# Motors.net
KiCad netlist of a schematic drawn in Altium Designer
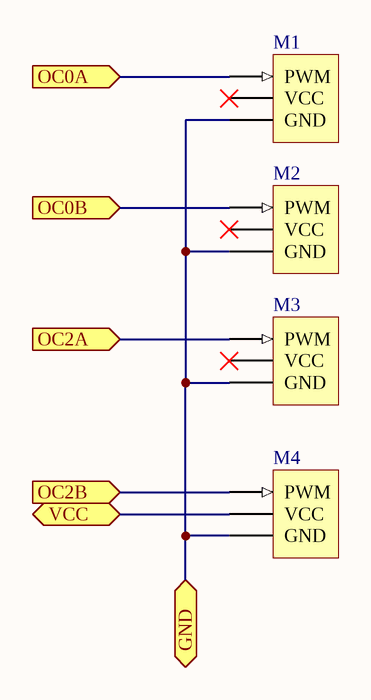
[diagram p0: Motors.SchDoc]

(export (version "E")
  (design (tool "Eeschema 10.0.6"))
  (components
    (comp (ref "M1")
      (value "Header 3")
      (footprint "HDR1X3")
      (description "Header, 3-Pin")
      (fields (field (name "PUBLISHER") "Altium Limited"))
      (libsource (lib "Miscellaneous Connectors") (part "Header 3"))
    )
    (comp (ref "M2")
      (value "Header 3")
      (footprint "HDR1X3")
      (description "Header, 3-Pin")
      (fields (field (name "PUBLISHER") "Altium Limited"))
      (libsource (lib "Miscellaneous Connectors") (part "Header 3"))
    )
    (comp (ref "M3")
      (value "Header 3")
      (footprint "HDR1X3")
      (description "Header, 3-Pin")
      (fields (field (name "PUBLISHER") "Altium Limited"))
      (libsource (lib "Miscellaneous Connectors") (part "Header 3"))
    )
    (comp (ref "M4")
      (value "Header 3")
      (footprint "HDR1X3")
      (description "Header, 3-Pin")
      (fields (field (name "PUBLISHER") "Altium Limited"))
      (libsource (lib "Miscellaneous Connectors") (part "Header 3"))
    )
  )
  (nets
    (net (code "1") (name "/GND") (class "Default")
      (node (ref "M1") (pin "3") (pinfunction "GND_3") (pintype "power_in"))
      (node (ref "M2") (pin "3") (pinfunction "GND_3") (pintype "power_in"))
      (node (ref "M3") (pin "3") (pinfunction "GND_3") (pintype "power_in"))
      (node (ref "M4") (pin "3") (pinfunction "GND_3") (pintype "power_in"))
    )
    (net (code "2") (name "/OC0A") (class "Default")
      (node (ref "M1") (pin "1") (pinfunction "PWM_1") (pintype "input"))
    )
    (net (code "3") (name "/OC0B") (class "Default")
      (node (ref "M2") (pin "1") (pinfunction "PWM_1") (pintype "input"))
    )
    (net (code "4") (name "/OC2A") (class "Default")
      (node (ref "M3") (pin "1") (pinfunction "PWM_1") (pintype "input"))
    )
    (net (code "5") (name "/OC2B") (class "Default")
      (node (ref "M4") (pin "1") (pinfunction "PWM_1") (pintype "input"))
    )
    (net (code "6") (name "/VCC") (class "Default")
      (node (ref "M4") (pin "2") (pinfunction "VCC_2") (pintype "power_in"))
    )
    (net (code "7") (name "unconnected-(M1-VCC-Pad2)") (class "Default")
      (node (ref "M1") (pin "2") (pinfunction "VCC_2") (pintype "power_in+no_connect"))
    )
    (net (code "8") (name "unconnected-(M2-VCC-Pad2)") (class "Default")
      (node (ref "M2") (pin "2") (pinfunction "VCC_2") (pintype "power_in+no_connect"))
    )
    (net (code "9") (name "unconnected-(M3-VCC-Pad2)") (class "Default")
      (node (ref "M3") (pin "2") (pinfunction "VCC_2") (pintype "power_in+no_connect"))
    )
  )
)
